# Ej4Electro3.net
KiCad netlist of a schematic drawn in Altium Designer
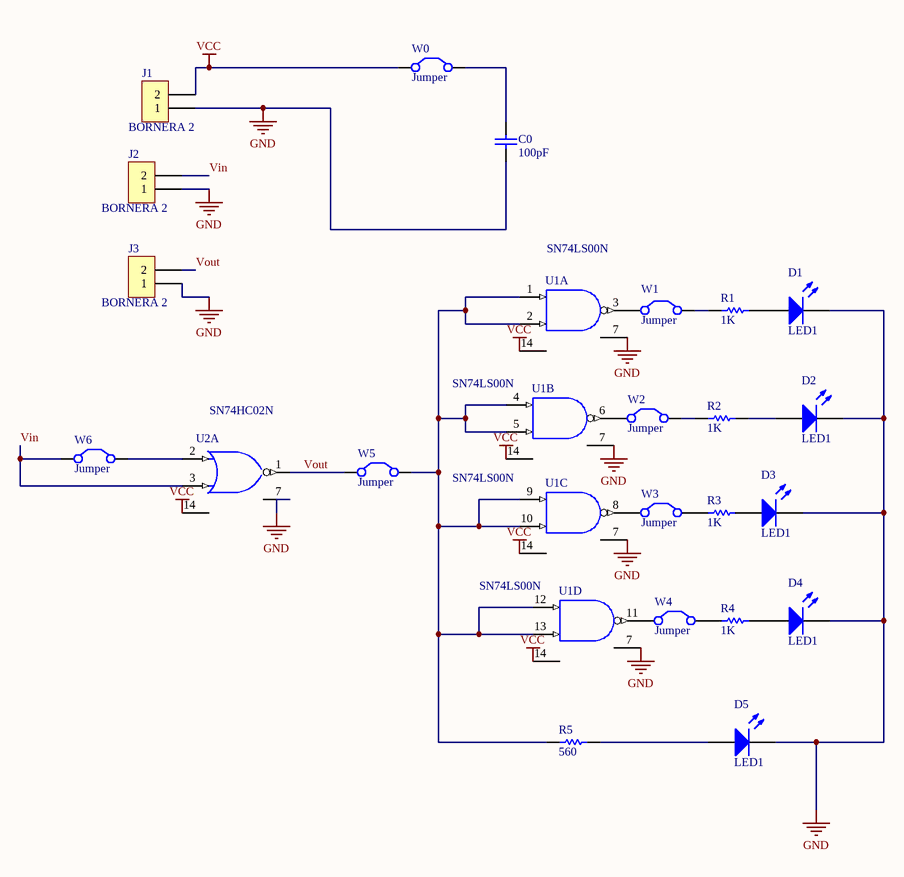
[diagram p0: Ej4Electro3.SchDoc]

(export (version "E")
  (design (tool "Eeschema 10.0.6"))
  (components
    (comp (ref "C0")
      (value "100pF")
      (footprint "RAD-0.3")
      (description "Capacitor")
      (fields (field (name "PUBLISHER") "Altium Limited"))
      (libsource (lib "Miscellaneous Devices") (part "Cap"))
    )
    (comp (ref "D1")
      (value "LED1")
      (footprint "LED-1")
      (description "Typical RED GaAs LED")
      (fields (field (name "PUBLISHER") "Altium Limited"))
      (libsource (lib "Miscellaneous Devices") (part "LED1"))
    )
    (comp (ref "D2")
      (value "LED1")
      (footprint "LED-1")
      (description "Typical RED GaAs LED")
      (fields (field (name "PUBLISHER") "Altium Limited"))
      (libsource (lib "Miscellaneous Devices") (part "LED1"))
    )
    (comp (ref "D3")
      (value "LED1")
      (footprint "LED-1")
      (description "Typical RED GaAs LED")
      (fields (field (name "PUBLISHER") "Altium Limited"))
      (libsource (lib "Miscellaneous Devices") (part "LED1"))
    )
    (comp (ref "D4")
      (value "LED1")
      (footprint "LED-1")
      (description "Typical RED GaAs LED")
      (fields (field (name "PUBLISHER") "Altium Limited"))
      (libsource (lib "Miscellaneous Devices") (part "LED1"))
    )
    (comp (ref "D5")
      (value "LED1")
      (footprint "LED-1")
      (description "Typical RED GaAs LED")
      (fields (field (name "PUBLISHER") "Altium Limited"))
      (libsource (lib "Miscellaneous Devices") (part "LED1"))
    )
    (comp (ref "J1")
      (value "BORNERA 2")
      (footprint "BORNERA2")
      (libsource (lib "LIBEBAL") (part "BORNERA 2"))
    )
    (comp (ref "J2")
      (value "BORNERA 2")
      (footprint "BORNERA2")
      (libsource (lib "LIBEBAL") (part "BORNERA 2"))
    )
    (comp (ref "J3")
      (value "BORNERA 2")
      (footprint "BORNERA2")
      (libsource (lib "LIBEBAL") (part "BORNERA 2"))
    )
    (comp (ref "R1")
      (value "1K")
      (footprint "AXIAL-0.3")
      (description "Resistor")
      (fields (field (name "PUBLISHER") "Altium Limited"))
      (libsource (lib "Miscellaneous Devices") (part "Res1"))
    )
    (comp (ref "R2")
      (value "1K")
      (footprint "AXIAL-0.3")
      (description "Resistor")
      (fields (field (name "PUBLISHER") "Altium Limited"))
      (libsource (lib "Miscellaneous Devices") (part "Res1"))
    )
    (comp (ref "R3")
      (value "1K")
      (footprint "AXIAL-0.3")
      (description "Resistor")
      (fields (field (name "PUBLISHER") "Altium Limited"))
      (libsource (lib "Miscellaneous Devices") (part "Res1"))
    )
    (comp (ref "R4")
      (value "1K")
      (footprint "AXIAL-0.3")
      (description "Resistor")
      (fields (field (name "PUBLISHER") "Altium Limited"))
      (libsource (lib "Miscellaneous Devices") (part "Res1"))
    )
    (comp (ref "R5")
      (value "560")
      (footprint "AXIAL-0.3")
      (description "Resistor")
      (fields (field (name "PUBLISHER") "Altium Limited"))
      (libsource (lib "Miscellaneous Devices") (part "Res1"))
    )
    (comp (ref "U1")
      (value "SN74LS00N")
      (footprint "N014")
      (description "Quadruple 2-Input Positive-NAND Gate")
      (fields (field (name "PUBLISHER") "Altium Limited"))
      (libsource (lib "TI Logic Gate 2") (part "SN74LS00N"))
    )
    (comp (ref "U2")
      (value "SN74HC02N")
      (footprint "N014")
      (description "Quadruple 2-Input Positive-NOR Gate")
      (fields (field (name "PUBLISHER") "Altium Limited"))
      (libsource (lib "TI Logic Gate 2") (part "SN74HC02N"))
    )
    (comp (ref "W0")
      (value "Jumper")
      (footprint "RAD-0.2")
      (description "Jumper Wire")
      (fields (field (name "PUBLISHER") "Altium Limited"))
      (libsource (lib "Miscellaneous Devices") (part "Jumper"))
    )
    (comp (ref "W1")
      (value "Jumper")
      (footprint "RAD-0.2")
      (description "Jumper Wire")
      (fields (field (name "PUBLISHER") "Altium Limited"))
      (libsource (lib "Miscellaneous Devices") (part "Jumper"))
    )
    (comp (ref "W2")
      (value "Jumper")
      (footprint "RAD-0.2")
      (description "Jumper Wire")
      (fields (field (name "PUBLISHER") "Altium Limited"))
      (libsource (lib "Miscellaneous Devices") (part "Jumper"))
    )
    (comp (ref "W3")
      (value "Jumper")
      (footprint "RAD-0.2")
      (description "Jumper Wire")
      (fields (field (name "PUBLISHER") "Altium Limited"))
      (libsource (lib "Miscellaneous Devices") (part "Jumper"))
    )
    (comp (ref "W4")
      (value "Jumper")
      (footprint "RAD-0.2")
      (description "Jumper Wire")
      (fields (field (name "PUBLISHER") "Altium Limited"))
      (libsource (lib "Miscellaneous Devices") (part "Jumper"))
    )
    (comp (ref "W5")
      (value "Jumper")
      (footprint "RAD-0.2")
      (description "Jumper Wire")
      (fields (field (name "PUBLISHER") "Altium Limited"))
      (libsource (lib "Miscellaneous Devices") (part "Jumper"))
    )
    (comp (ref "W6")
      (value "Jumper")
      (footprint "RAD-0.2")
      (description "Jumper Wire")
      (fields (field (name "PUBLISHER") "Altium Limited"))
      (libsource (lib "Miscellaneous Devices") (part "Jumper"))
    )
  )
  (nets
    (net (code "1") (name "/Vin") (class "Default")
      (node (ref "J2") (pin "2") (pinfunction "2_2") (pintype "passive"))
      (node (ref "U2") (pin "3") (pinfunction "B_3") (pintype "input"))
      (node (ref "W6") (pin "1") (pinfunction "C1_1") (pintype "passive"))
    )
    (net (code "2") (name "/Vout") (class "Default")
      (node (ref "J3") (pin "2") (pinfunction "2_2") (pintype "passive"))
      (node (ref "U2") (pin "1") (pinfunction "Y_1") (pintype "output"))
      (node (ref "W5") (pin "1") (pinfunction "C1_1") (pintype "passive"))
    )
    (net (code "3") (name "GND") (class "Default")
      (node (ref "C0") (pin "1") (pinfunction "1_1") (pintype "passive"))
      (node (ref "D1") (pin "2") (pinfunction "K_2") (pintype "passive"))
      (node (ref "D2") (pin "2") (pinfunction "K_2") (pintype "passive"))
      (node (ref "D3") (pin "2") (pinfunction "K_2") (pintype "passive"))
      (node (ref "D4") (pin "2") (pinfunction "K_2") (pintype "passive"))
      (node (ref "D5") (pin "2") (pinfunction "K_2") (pintype "passive"))
      (node (ref "J1") (pin "1") (pinfunction "1_1") (pintype "passive"))
      (node (ref "J2") (pin "1") (pinfunction "1_1") (pintype "passive"))
      (node (ref "J3") (pin "1") (pinfunction "1_1") (pintype "passive"))
      (node (ref "U1") (pin "7") (pinfunction "GND_7") (pintype "power_in"))
      (node (ref "U2") (pin "7") (pinfunction "GND_7") (pintype "power_in"))
    )
    (net (code "4") (name "Net-(D1-A)") (class "Default")
      (node (ref "D1") (pin "1") (pinfunction "A_1") (pintype "passive"))
      (node (ref "R1") (pin "2") (pinfunction "2_2") (pintype "passive"))
    )
    (net (code "5") (name "Net-(D2-A)") (class "Default")
      (node (ref "D2") (pin "1") (pinfunction "A_1") (pintype "passive"))
      (node (ref "R2") (pin "2") (pinfunction "2_2") (pintype "passive"))
    )
    (net (code "6") (name "Net-(D3-A)") (class "Default")
      (node (ref "D3") (pin "1") (pinfunction "A_1") (pintype "passive"))
      (node (ref "R3") (pin "2") (pinfunction "2_2") (pintype "passive"))
    )
    (net (code "7") (name "Net-(D4-A)") (class "Default")
      (node (ref "D4") (pin "1") (pinfunction "A_1") (pintype "passive"))
      (node (ref "R4") (pin "2") (pinfunction "2_2") (pintype "passive"))
    )
    (net (code "8") (name "Net-(D5-A)") (class "Default")
      (node (ref "D5") (pin "1") (pinfunction "A_1") (pintype "passive"))
      (node (ref "R5") (pin "2") (pinfunction "2_2") (pintype "passive"))
    )
    (net (code "9") (name "Net-(U1A-A)") (class "Default")
      (node (ref "R5") (pin "1") (pinfunction "1_1") (pintype "passive"))
      (node (ref "U1") (pin "1") (pinfunction "A_1") (pintype "input"))
      (node (ref "U1") (pin "10") (pinfunction "B_10") (pintype "input"))
      (node (ref "U1") (pin "12") (pinfunction "A_12") (pintype "input"))
      (node (ref "U1") (pin "13") (pinfunction "B_13") (pintype "input"))
      (node (ref "U1") (pin "2") (pinfunction "B_2") (pintype "input"))
      (node (ref "U1") (pin "4") (pinfunction "A_4") (pintype "input"))
      (node (ref "U1") (pin "5") (pinfunction "B_5") (pintype "input"))
      (node (ref "U1") (pin "9") (pinfunction "A_9") (pintype "input"))
      (node (ref "W5") (pin "2") (pinfunction "C2_2") (pintype "passive"))
    )
    (net (code "10") (name "Net-(U1A-Y)") (class "Default")
      (node (ref "U1") (pin "3") (pinfunction "Y_3") (pintype "output"))
      (node (ref "W1") (pin "1") (pinfunction "C1_1") (pintype "passive"))
    )
    (net (code "11") (name "Net-(U1B-Y)") (class "Default")
      (node (ref "U1") (pin "6") (pinfunction "Y_6") (pintype "output"))
      (node (ref "W2") (pin "1") (pinfunction "C1_1") (pintype "passive"))
    )
    (net (code "12") (name "Net-(U1C-Y)") (class "Default")
      (node (ref "U1") (pin "8") (pinfunction "Y_8") (pintype "output"))
      (node (ref "W3") (pin "1") (pinfunction "C1_1") (pintype "passive"))
    )
    (net (code "13") (name "Net-(U1D-Y)") (class "Default")
      (node (ref "U1") (pin "11") (pinfunction "Y_11") (pintype "output"))
      (node (ref "W4") (pin "1") (pinfunction "C1_1") (pintype "passive"))
    )
    (net (code "14") (name "Net-(U2A-A)") (class "Default")
      (node (ref "U2") (pin "2") (pinfunction "A_2") (pintype "input"))
      (node (ref "W6") (pin "2") (pinfunction "C2_2") (pintype "passive"))
    )
    (net (code "15") (name "Net-(W0-C2)") (class "Default")
      (node (ref "C0") (pin "2") (pinfunction "2_2") (pintype "passive"))
      (node (ref "W0") (pin "2") (pinfunction "C2_2") (pintype "passive"))
    )
    (net (code "16") (name "Net-(W1-C2)") (class "Default")
      (node (ref "R1") (pin "1") (pinfunction "1_1") (pintype "passive"))
      (node (ref "W1") (pin "2") (pinfunction "C2_2") (pintype "passive"))
    )
    (net (code "17") (name "Net-(W2-C2)") (class "Default")
      (node (ref "R2") (pin "1") (pinfunction "1_1") (pintype "passive"))
      (node (ref "W2") (pin "2") (pinfunction "C2_2") (pintype "passive"))
    )
    (net (code "18") (name "Net-(W3-C2)") (class "Default")
      (node (ref "R3") (pin "1") (pinfunction "1_1") (pintype "passive"))
      (node (ref "W3") (pin "2") (pinfunction "C2_2") (pintype "passive"))
    )
    (net (code "19") (name "Net-(W4-C2)") (class "Default")
      (node (ref "R4") (pin "1") (pinfunction "1_1") (pintype "passive"))
      (node (ref "W4") (pin "2") (pinfunction "C2_2") (pintype "passive"))
    )
    (net (code "20") (name "VCC") (class "Default")
      (node (ref "J1") (pin "2") (pinfunction "2_2") (pintype "passive"))
      (node (ref "U1") (pin "14") (pinfunction "VCC_14") (pintype "power_in"))
      (node (ref "U2") (pin "14") (pinfunction "VCC_14") (pintype "power_in"))
      (node (ref "W0") (pin "1") (pinfunction "C1_1") (pintype "passive"))
    )
  )
)
